# DB_Power-X03.net
KiCad netlist of a schematic drawn in Altium Designer
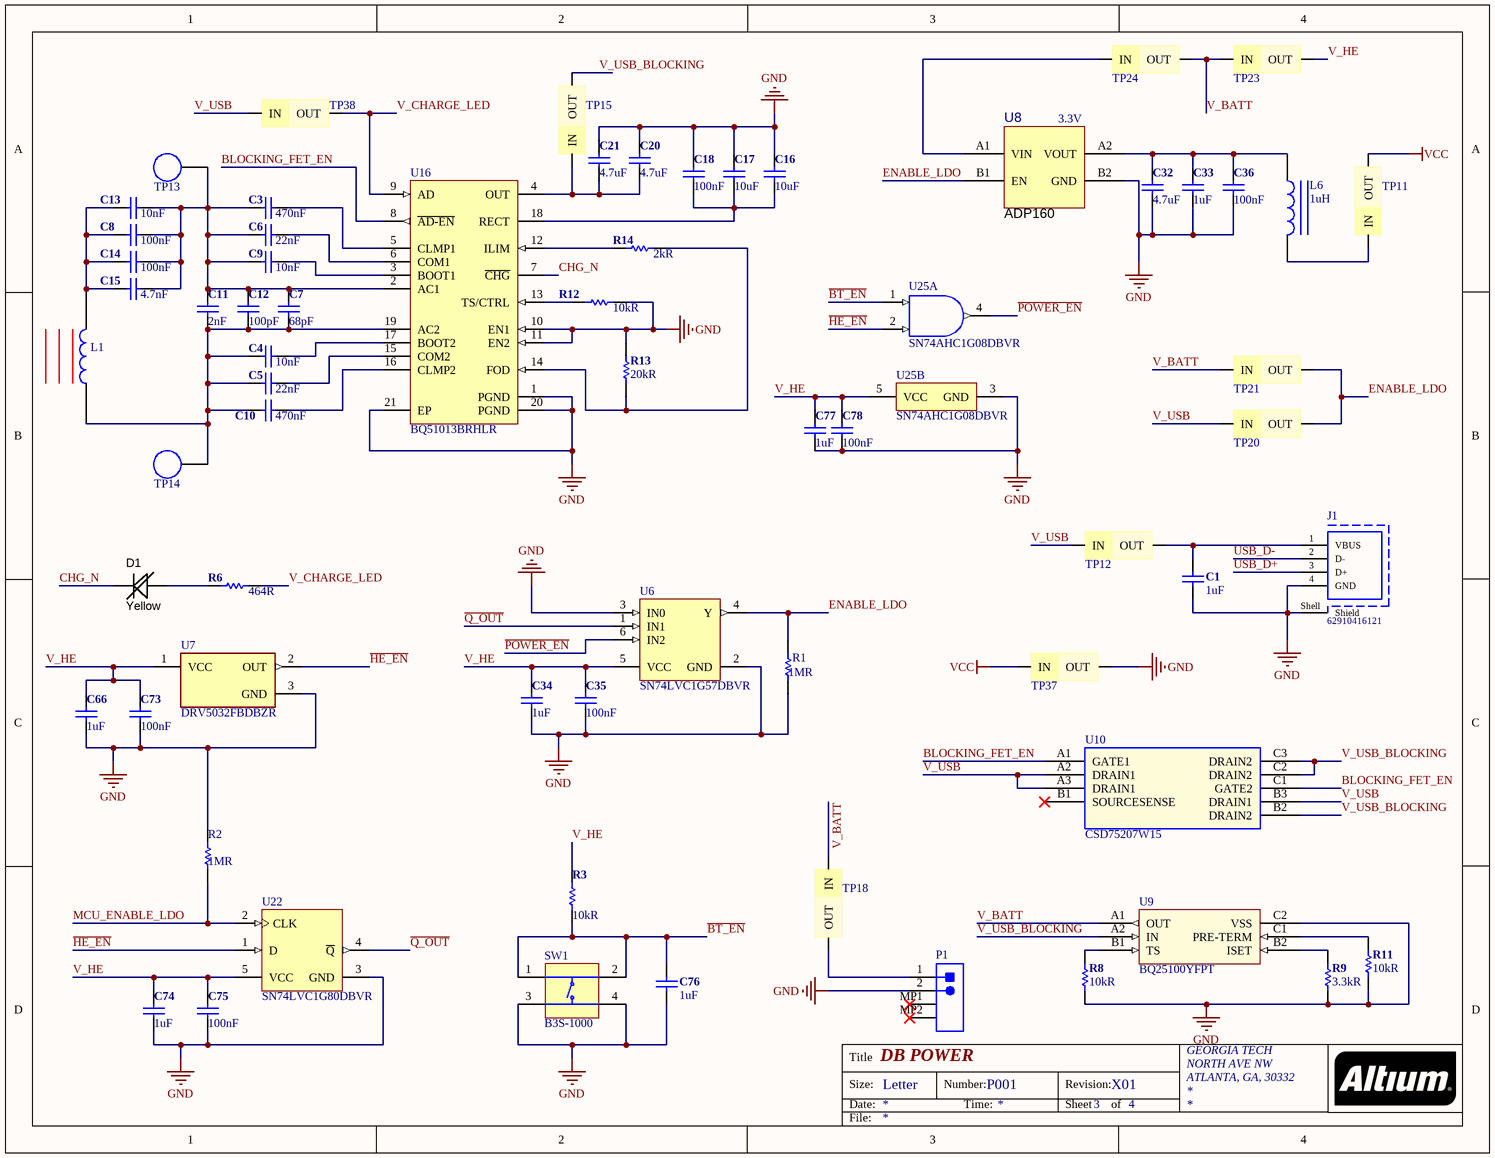
[diagram p0: DB_Power-X03.SchDoc]

(export (version "E")
  (design (tool "Eeschema 10.0.6"))
  (components
    (comp (ref "C1")
      (value "1uF")
      (footprint "C0402")
      (fields
        (field (name "MANUFACTURER") "Yageo")
        (field (name "MANUFACTURER PART NUMBER") "CC0402MRX5R5BB105")
        (field (name "TOLERANCE") "20%")
      )
      (libsource (lib "DB-X01") (part "C-0402(1005)"))
    )
    (comp (ref "C3")
      (value "470nF")
      (footprint "C0402")
      (fields
        (field (name "MANUFACTURER") "Murata")
        (field (name "MANUFACTURER PART NUMBER") "GRT155R61E474ME01D")
        (field (name "TOLERANCE") "20%")
      )
      (libsource (lib "DB-X01") (part "C-0402(1005)"))
    )
    (comp (ref "C4")
      (value "10nF")
      (footprint "C0402")
      (fields
        (field (name "MANUFACTURER") "KEMET")
        (field (name "MANUFACTURER PART NUMBER") "C0402C103J3RACTU")
        (field (name "TOLERANCE") "5%")
      )
      (libsource (lib "DB-X01") (part "C-0402(1005)"))
    )
    (comp (ref "C5")
      (value "22nF")
      (footprint "C0402")
      (fields
        (field (name "MANUFACTURER") "Murata")
        (field (name "MANUFACTURER PART NUMBER") "GRM155R71E223KA61D")
        (field (name "TOLERANCE") "10%")
      )
      (libsource (lib "DB-X01") (part "C-0402(1005)"))
    )
    (comp (ref "C6")
      (value "22nF")
      (footprint "C0402")
      (fields
        (field (name "MANUFACTURER") "Murata")
        (field (name "MANUFACTURER PART NUMBER") "GRM155R71E223KA61D")
        (field (name "TOLERANCE") "10%")
      )
      (libsource (lib "DB-X01") (part "C-0402(1005)"))
    )
    (comp (ref "C7")
      (value "68pF")
      (footprint "C0402")
      (fields
        (field (name "MANUFACTURER") "KEMET")
        (field (name "MANUFACTURER PART NUMBER") "CBR04C680F3GAC")
        (field (name "TOLERANCE") "1%")
      )
      (libsource (lib "DB-X01") (part "C-0402(1005)"))
    )
    (comp (ref "C8")
      (value "100nF")
      (footprint "C0402")
      (fields
        (field (name "MANUFACTURER") "Taiyo Yuden")
        (field (name "MANUFACTURER PART NUMBER") "TMK105BJ104KV-F")
        (field (name "TOLERANCE") "10%")
      )
      (libsource (lib "DB-X01") (part "C-0402(1005)"))
    )
    (comp (ref "C9")
      (value "10nF")
      (footprint "C0402")
      (fields
        (field (name "MANUFACTURER") "KEMET")
        (field (name "MANUFACTURER PART NUMBER") "C0402C103J3RACTU")
        (field (name "TOLERANCE") "5%")
      )
      (libsource (lib "DB-X01") (part "C-0402(1005)"))
    )
    (comp (ref "C10")
      (value "470nF")
      (footprint "C0402")
      (fields
        (field (name "MANUFACTURER") "Murata")
        (field (name "MANUFACTURER PART NUMBER") "GRT155R61E474ME01D")
        (field (name "TOLERANCE") "20%")
      )
      (libsource (lib "DB-X01") (part "C-0402(1005)"))
    )
    (comp (ref "C11")
      (value "2nF")
      (footprint "C0402")
      (fields
        (field (name "MANUFACTURER") "KEMET")
        (field (name "MANUFACTURER PART NUMBER") "C0402C202J3GACTU")
        (field (name "TOLERANCE") "5%")
      )
      (libsource (lib "DB-X01") (part "C-0402(1005)"))
    )
    (comp (ref "C12")
      (value "100pF")
      (footprint "C0402")
      (fields
        (field (name "MANUFACTURER") "KEMET")
        (field (name "MANUFACTURER PART NUMBER") "CBR04C101F3GAC")
        (field (name "TOLERANCE") "1%")
      )
      (libsource (lib "DB-X01") (part "C-0402(1005)"))
    )
    (comp (ref "C13")
      (value "10nF")
      (footprint "C0402")
      (fields
        (field (name "MANUFACTURER") "Yageo")
        (field (name "MANUFACTURER PART NUMBER") "CC0402JRX7R8BB103")
        (field (name "TOLERANCE") "5%")
      )
      (libsource (lib "DB-X01") (part "C-0402(1005)"))
    )
    (comp (ref "C14")
      (value "100nF")
      (footprint "C0402")
      (fields
        (field (name "MANUFACTURER") "Taiyo Yuden")
        (field (name "MANUFACTURER PART NUMBER") "TMK105BJ104KV-F")
        (field (name "TOLERANCE") "10%")
      )
      (libsource (lib "DB-X01") (part "C-0402(1005)"))
    )
    (comp (ref "C15")
      (value "4.7nF")
      (footprint "C0402")
      (fields
        (field (name "MANUFACTURER") "Yageo")
        (field (name "MANUFACTURER PART NUMBER") "CC0402JRX7R8BB472")
        (field (name "TOLERANCE") "5%")
      )
      (libsource (lib "DB-X01") (part "C-0402(1005)"))
    )
    (comp (ref "C16")
      (value "10uF")
      (footprint "C0603")
      (fields
        (field (name "MANUFACTURER") "Murata")
        (field (name "MANUFACTURER PART NUMBER") "GRM188R61E106MA73J")
        (field (name "TOLERANCE") "20%")
      )
      (libsource (lib "DB-X01") (part "C-0603(1608)"))
    )
    (comp (ref "C17")
      (value "10uF")
      (footprint "C0603")
      (fields
        (field (name "MANUFACTURER") "Murata")
        (field (name "MANUFACTURER PART NUMBER") "GRM188R61E106MA73J")
        (field (name "TOLERANCE") "20%")
      )
      (libsource (lib "DB-X01") (part "C-0603(1608)"))
    )
    (comp (ref "C18")
      (value "100nF")
      (footprint "C0603")
      (fields
        (field (name "MANUFACTURER") "Yageo")
        (field (name "MANUFACTURER PART NUMBER") "CC0402ZRY5V8BB104")
        (field (name "TOLERANCE") "80%")
      )
      (libsource (lib "DB-X01") (part "C-0603(1608)"))
    )
    (comp (ref "C20")
      (value "4.7uF")
      (footprint "C0402")
      (description "0402 10 V 4.7 uF ±20% Tolerance X5R Multilayer Ceramic Chip Capacitor")
      (fields
        (field (name "MANUFACTURER") "Murata")
        (field (name "MANUFACTURER PART NUMBER") "GRM155R61A475MEAAD")
      )
      (libsource (lib "DB-X01") (part "C-0402(1005)"))
    )
    (comp (ref "C21")
      (value "4.7uF")
      (footprint "C0402")
      (description "0402 10 V 4.7 uF ±20% Tolerance X5R Multilayer Ceramic Chip Capacitor")
      (fields
        (field (name "MANUFACTURER") "Murata")
        (field (name "MANUFACTURER PART NUMBER") "GRM155R61A475MEAAD")
      )
      (libsource (lib "DB-X01") (part "C-0402(1005)"))
    )
    (comp (ref "C32")
      (value "4.7uF")
      (footprint "C0402")
      (description "0402 10 V 4.7 uF ±20% Tolerance X5R Multilayer Ceramic Chip Capacitor")
      (fields
        (field (name "MANUFACTURER") "Murata")
        (field (name "MANUFACTURER PART NUMBER") "GRM155R61A475MEAAD")
      )
      (libsource (lib "DB-X01") (part "C-0402(1005)"))
    )
    (comp (ref "C33")
      (value "1uF")
      (footprint "C0402")
      (fields
        (field (name "MANUFACTURER") "Yageo")
        (field (name "MANUFACTURER PART NUMBER") "CC0402MRX5R5BB105")
        (field (name "TOLERANCE") "20%")
      )
      (libsource (lib "DB-X01") (part "C-0402(1005)"))
    )
    (comp (ref "C34")
      (value "1uF")
      (footprint "C0402")
      (fields
        (field (name "MANUFACTURER") "Yageo")
        (field (name "MANUFACTURER PART NUMBER") "CC0402MRX5R5BB105")
        (field (name "TOLERANCE") "20%")
      )
      (libsource (lib "DB-X01") (part "C-0402(1005)"))
    )
    (comp (ref "C35")
      (value "100nF")
      (footprint "C0402")
      (fields
        (field (name "MANUFACTURER") "Taiyo Yuden")
        (field (name "MANUFACTURER PART NUMBER") "TMK105BJ104KV-F")
        (field (name "TOLERANCE") "10%")
      )
      (libsource (lib "DB-X01") (part "C-0402(1005)"))
    )
    (comp (ref "C36")
      (value "100nF")
      (footprint "C0402")
      (fields
        (field (name "MANUFACTURER") "Taiyo Yuden")
        (field (name "MANUFACTURER PART NUMBER") "TMK105BJ104KV-F")
        (field (name "TOLERANCE") "10%")
      )
      (libsource (lib "DB-X01") (part "C-0402(1005)"))
    )
    (comp (ref "C66")
      (value "1uF")
      (footprint "C0402")
      (fields
        (field (name "MANUFACTURER") "Yageo")
        (field (name "MANUFACTURER PART NUMBER") "CC0402MRX5R5BB105")
        (field (name "TOLERANCE") "20%")
      )
      (libsource (lib "DB-X01") (part "C-0402(1005)"))
    )
    (comp (ref "C73")
      (value "100nF")
      (footprint "C0402")
      (fields
        (field (name "MANUFACTURER") "Taiyo Yuden")
        (field (name "MANUFACTURER PART NUMBER") "TMK105BJ104KV-F")
        (field (name "TOLERANCE") "10%")
      )
      (libsource (lib "DB-X01") (part "C-0402(1005)"))
    )
    (comp (ref "C74")
      (value "1uF")
      (footprint "C0402")
      (fields
        (field (name "MANUFACTURER") "Yageo")
        (field (name "MANUFACTURER PART NUMBER") "CC0402MRX5R5BB105")
        (field (name "TOLERANCE") "20%")
      )
      (libsource (lib "DB-X01") (part "C-0402(1005)"))
    )
    (comp (ref "C75")
      (value "100nF")
      (footprint "C0402")
      (fields
        (field (name "MANUFACTURER") "Taiyo Yuden")
        (field (name "MANUFACTURER PART NUMBER") "TMK105BJ104KV-F")
        (field (name "TOLERANCE") "10%")
      )
      (libsource (lib "DB-X01") (part "C-0402(1005)"))
    )
    (comp (ref "C76")
      (value "1uF")
      (footprint "C0402")
      (fields
        (field (name "MANUFACTURER") "Yageo")
        (field (name "MANUFACTURER PART NUMBER") "CC0402MRX5R5BB105")
        (field (name "TOLERANCE") "20%")
      )
      (libsource (lib "DB-X01") (part "C-0402(1005)"))
    )
    (comp (ref "C77")
      (value "1uF")
      (footprint "C0402")
      (fields
        (field (name "MANUFACTURER") "Yageo")
        (field (name "MANUFACTURER PART NUMBER") "CC0402MRX5R5BB105")
        (field (name "TOLERANCE") "20%")
      )
      (libsource (lib "DB-X01") (part "C-0402(1005)"))
    )
    (comp (ref "C78")
      (value "100nF")
      (footprint "C0402")
      (fields
        (field (name "MANUFACTURER") "Taiyo Yuden")
        (field (name "MANUFACTURER PART NUMBER") "TMK105BJ104KV-F")
        (field (name "TOLERANCE") "10%")
      )
      (libsource (lib "DB-X01") (part "C-0402(1005)"))
    )
    (comp (ref "D1")
      (value "Yellow")
      (footprint "LED_0402")
      (description "Single Color LED, Super Bright Yellow, Water Clear, 0.8mm")
      (fields
        (field (name "MANUFACTURER") "Kingbright")
        (field (name "MANUFACTURER PART NUMBER") "APHHS1005SYCK")
      )
      (libsource (lib "DB-X01") (part "LED_0402(1005)"))
    )
    (comp (ref "J1")
      (value "62910416121")
      (footprint "62910416121")
      (description "USB 2.0 Type B Receptacle WR-COM, Horizontal, SMT, with Pads and Pegs")
      (fields (field (name "MANUFACTURER") "Wurth Electronics"))
      (libsource (lib "Altium Content Vault") (part "WE-USB-4-1SHLD"))
    )
    (comp (ref "L1")
      (value "WIRELESS CHARGING COIL, RECEIVER")
      (footprint "760308101219")
      (description "General Purpose Inductor, 11.8uH, 10%, 1 Element")
      (fields
        (field (name "MANUFACTURER") "Wurth Electronics")
        (field (name "MANUFACTURER PART NUMBER") "760308101219")
      )
      (libsource (lib "DB-X01") (part "WIRELESS_CHARGING_COIL"))
    )
    (comp (ref "L6")
      (value "1uH")
      (footprint "L0402")
      (description "General Purpose Inductor, 1uH, 20%, 1 Element, Ferrite-Core, SMD, 0402")
      (fields
        (field (name "MANUFACTURER") "TDK")
        (field (name "MANUFACTURER PART NUMBER") "MLZ1005M1R0WT000")
      )
      (libsource (lib "DB-X01") (part "Inductor Iron"))
    )
    (comp (ref "P1")
      (value "B2B-PH-SM4-TB(LF)(SN)")
      (footprint "JST-B2B-PH-SM4-TB-2_V")
      (description "Male Header, Pitch 2 mm, 1 x 2 Position, Height 6.6 mm, RoHS, Tape and Reel")
      (fields (field (name "MANUFACTURER") "JST"))
      (libsource (lib "Altium Content Vault") (part "CN-1P-2M-R2"))
    )
    (comp (ref "R1")
      (value "AC0402FR-071ML")
      (footprint "RESC1005X37X25LL05T10")
      (description "100 ohm resistor")
      (fields
        (field (name "MANUFACTURER") "Yageo")
        (field (name "RESISTANCE") "1MR")
        (field (name "TOLERANCE") "1%")
      )
      (libsource (lib "Altium Content Vault") (part "RES"))
    )
    (comp (ref "R2")
      (value "AC0402FR-071ML")
      (footprint "RESC1005X37X25LL05T10")
      (description "100 ohm resistor")
      (fields
        (field (name "MANUFACTURER") "Yageo")
        (field (name "RESISTANCE") "1MR")
        (field (name "TOLERANCE") "1%")
      )
      (libsource (lib "Altium Content Vault") (part "RES"))
    )
    (comp (ref "R3")
      (value "10kR")
      (footprint "R0402")
      (fields
        (field (name "MANUFACTURER") "Yageo")
        (field (name "MANUFACTURER PART NUMBER") "AC0402FR-0710KL")
        (field (name "TOLERANCE") "1%")
      )
      (libsource (lib "DB-X01") (part "R-0402(1005)"))
    )
    (comp (ref "R6")
      (value "464R")
      (footprint "R0402")
      (fields
        (field (name "MANUFACTURER") "Yageo")
        (field (name "MANUFACTURER PART NUMBER") "RC0402FR-07464RL")
        (field (name "TOLERANCE") "1%")
      )
      (libsource (lib "DB-X01") (part "R-0402(1005)"))
    )
    (comp (ref "R8")
      (value "10kR")
      (footprint "R0402")
      (fields
        (field (name "MANUFACTURER") "Yageo")
        (field (name "MANUFACTURER PART NUMBER") "AC0402FR-0710KL")
        (field (name "TOLERANCE") "1%")
      )
      (libsource (lib "DB-X01") (part "R-0402(1005)"))
    )
    (comp (ref "R9")
      (value "3.3kR")
      (footprint "R0402")
      (fields
        (field (name "MANUFACTURER") "Yageo")
        (field (name "MANUFACTURER PART NUMBER") "AC0402FR-073K3L")
        (field (name "TOLERANCE") "1%")
      )
      (libsource (lib "DB-X01") (part "R-0402(1005)"))
    )
    (comp (ref "R11")
      (value "10kR")
      (footprint "R0402")
      (fields
        (field (name "MANUFACTURER") "Yageo")
        (field (name "MANUFACTURER PART NUMBER") "AC0402FR-0710KL")
        (field (name "TOLERANCE") "1%")
      )
      (libsource (lib "DB-X01") (part "R-0402(1005)"))
    )
    (comp (ref "R12")
      (value "10kR")
      (footprint "R0402")
      (fields
        (field (name "MANUFACTURER") "Yageo")
        (field (name "MANUFACTURER PART NUMBER") "AC0402FR-0710KL")
        (field (name "TOLERANCE") "1%")
      )
      (libsource (lib "DB-X01") (part "R-0402(1005)"))
    )
    (comp (ref "R13")
      (value "20kR")
      (footprint "R0402")
      (fields
        (field (name "MANUFACTURER") "Yageo")
        (field (name "MANUFACTURER PART NUMBER") "AC0402FR-0720KL")
        (field (name "TOLERANCE") "1%")
      )
      (libsource (lib "DB-X01") (part "R-0402(1005)"))
    )
    (comp (ref "R14")
      (value "2kR")
      (footprint "R0402")
      (fields
        (field (name "MANUFACTURER") "Yageo")
        (field (name "MANUFACTURER PART NUMBER") "AC0402FR-072KL")
        (field (name "TOLERANCE") "1%")
      )
      (libsource (lib "DB-X01") (part "R-0402(1005)"))
    )
    (comp (ref "SW1")
      (value "B3S-1000")
      (footprint "OMRON-B3S-1000-4_V")
      (description "Sealed Tactile Switch, SPST-NO, 3 to 24 V, -25 to 70 degC, 4-Pin SMD, RoHS, Bulk")
      (fields (field (name "MANUFACTURER") "Omron") (field (name "MANUFACTURER PART NUMBER") "B3S-1000P"))
      (libsource (lib "Altium Content Vault") (part "SW-SPST-4_A"))
    )
    (comp (ref "TP11")
      (value "JUMPER")
      (footprint "JUMPER")
      (description "SHUNT LP W/HANDLE 2 POS 30AU")
      (fields
        (field (name "MANUFACTURER") "TE Connectivity")
        (field (name "MANUFACTURER PART NUMBER") "8815452")
      )
      (libsource (lib "DB-X01") (part "JUMPER"))
    )
    (comp (ref "TP12")
      (value "JUMPER")
      (footprint "JUMPER")
      (description "SHUNT LP W/HANDLE 2 POS 30AU")
      (fields
        (field (name "MANUFACTURER") "TE Connectivity")
        (field (name "MANUFACTURER PART NUMBER") "8815452")
      )
      (libsource (lib "") (part "JUMPER_2"))
    )
    (comp (ref "TP13")
      (value "S1751-46R")
      (footprint "S1751-46R")
      (description "PC TEST POINT TIN SMD")
      (fields (field (name "MANUFACTURER") "Harwin Inc."))
      (libsource (lib "DB-X01") (part "S1751-46R"))
    )
    (comp (ref "TP14")
      (value "S1751-46R")
      (footprint "S1751-46R")
      (description "PC TEST POINT TIN SMD")
      (fields (field (name "MANUFACTURER") "Harwin Inc."))
      (libsource (lib "DB-X01") (part "S1751-46R"))
    )
    (comp (ref "TP15")
      (value "JUMPER")
      (footprint "JUMPER")
      (description "SHUNT LP W/HANDLE 2 POS 30AU")
      (fields
        (field (name "MANUFACTURER") "TE Connectivity")
        (field (name "MANUFACTURER PART NUMBER") "8815452")
      )
      (libsource (lib "DB-X01") (part "JUMPER"))
    )
    (comp (ref "TP18")
      (value "JUMPER")
      (footprint "JUMPER")
      (description "SHUNT LP W/HANDLE 2 POS 30AU")
      (fields
        (field (name "MANUFACTURER") "TE Connectivity")
        (field (name "MANUFACTURER PART NUMBER") "8815452")
      )
      (libsource (lib "") (part "JUMPER_1"))
    )
    (comp (ref "TP20")
      (value "JUMPER")
      (footprint "JUMPER")
      (description "SHUNT LP W/HANDLE 2 POS 30AU")
      (fields
        (field (name "MANUFACTURER") "TE Connectivity")
        (field (name "MANUFACTURER PART NUMBER") "8815452")
      )
      (libsource (lib "") (part "JUMPER_2"))
    )
    (comp (ref "TP21")
      (value "JUMPER")
      (footprint "JUMPER")
      (description "SHUNT LP W/HANDLE 2 POS 30AU")
      (fields
        (field (name "MANUFACTURER") "TE Connectivity")
        (field (name "MANUFACTURER PART NUMBER") "8815452")
      )
      (libsource (lib "") (part "JUMPER_2"))
    )
    (comp (ref "TP23")
      (value "JUMPER")
      (footprint "JUMPER")
      (description "SHUNT LP W/HANDLE 2 POS 30AU")
      (fields
        (field (name "MANUFACTURER") "TE Connectivity")
        (field (name "MANUFACTURER PART NUMBER") "8815452")
      )
      (libsource (lib "DB-X02") (part "JUMPER"))
    )
    (comp (ref "TP24")
      (value "JUMPER")
      (footprint "JUMPER")
      (description "SHUNT LP W/HANDLE 2 POS 30AU")
      (fields
        (field (name "MANUFACTURER") "TE Connectivity")
        (field (name "MANUFACTURER PART NUMBER") "8815452")
      )
      (libsource (lib "DB-X02") (part "JUMPER"))
    )
    (comp (ref "TP37")
      (value "JUMPER")
      (footprint "JUMPER")
      (description "SHUNT LP W/HANDLE 2 POS 30AU")
      (fields
        (field (name "MANUFACTURER") "TE Connectivity")
        (field (name "MANUFACTURER PART NUMBER") "8815452")
      )
      (libsource (lib "DB-X02") (part "JUMPER"))
    )
    (comp (ref "TP38")
      (value "JUMPER")
      (footprint "JUMPER")
      (description "SHUNT LP W/HANDLE 2 POS 30AU")
      (fields
        (field (name "MANUFACTURER") "TE Connectivity")
        (field (name "MANUFACTURER PART NUMBER") "8815452")
      )
      (libsource (lib "DB-X02") (part "JUMPER"))
    )
    (comp (ref "U6")
      (value "SN74LVC1G57DBVR")
      (footprint "DBV0006A_M")
      (description "CONFIGURABLE MULTIPLE-FUNCTION GATE, DBV0006A, LARGE T&R")
      (fields (field (name "MANUFACTURER") "Texas Instruments"))
      (libsource (lib "Altium Content Vault") (part "TI-SN74XXX1GXX-6"))
    )
    (comp (ref "U7")
      (value "DRV5032FBDBZR")
      (footprint "FP-DBZ0003A-MFG")
      (description "LP HALL 32FBDBZR")
      (fields (field (name "MANUFACTURER") "Texas Instruments"))
      (libsource (lib "Altium Content Vault") (part "2ac151be60cf6bda0d169f73a696793"))
    )
    (comp (ref "U8")
      (value "ADP160")
      (footprint "ADP160")
      (description "Fixed Positive LDO Regulator, 3.3V, 0.195V Dropout, CMOS, PBGA4")
      (fields
        (field (name "MANUFACTURER") "Analog Devices")
        (field (name "MANUFACTURER PART NUMBER") "ADP160ACBZ-3.3-R7")
        (field (name "OUTPUT VOLTAGE") "3.3V")
      )
      (libsource (lib "DB-X01") (part "ADP160-3_3V"))
    )
    (comp (ref "U9")
      (value "BQ25100YFPT")
      (footprint "YZP0006")
      (description "Power Supply Support Circuit")
      (fields (field (name "MANUFACTURER") "Texas Instruments"))
      (libsource (lib "DB-X01") (part "BQ25100YFPT"))
    )
    (comp (ref "U10")
      (value "CSD75207W15")
      (footprint "YZF0009")
      (description "Small Signal Field-Effect Transistor, P-Channel, Metal-oxide Semiconductor FET")
      (fields (field (name "MANUFACTURER") "Texas Instruments"))
      (libsource (lib "DB-X01") (part "CSD75207W15"))
    )
    (comp (ref "U16")
      (value "BQ51013BRHLR")
      (footprint "BQ51013BRHLR")
      (fields (field (name "MANUFACTURER") "Texas Instruments"))
      (libsource (lib "DB-X01") (part "TI-BQ51013B-RHL20"))
    )
    (comp (ref "U22")
      (value "SN74LVC1G80DBVR")
      (footprint "DBV0005A_N")
      (description "Single Positive-Edge-Triggered D-Type Flip-Flop, DBV0005A, LARGE T&R")
      (fields (field (name "MANUFACTURER") "Texas Instruments"))
      (libsource (lib "Altium Content Vault") (part "TI-SN74XXX1G80-5"))
    )
    (comp (ref "U25")
      (value "SN74AHC1G08DBVR")
      (footprint "DBV0005A_N")
      (description "Single 2-Input Positive-AND Gate, DBV0005A, LARGE T&R")
      (fields (field (name "MANUFACTURER") "Texas Instruments"))
      (libsource (lib "Altium Content Vault") (part "TI-SN74XXX1X08-5"))
    )
  )
  (nets
    (net (code "1") (name "/BLOCKING_FET_EN") (class "Default")
      (node (ref "U10") (pin "A1") (pinfunction "GATE1_A1") (pintype "passive"))
      (node (ref "U10") (pin "C1") (pinfunction "GATE2_C1") (pintype "passive"))
      (node (ref "U16") (pin "8") (pinfunction "~{AD-EN}_8") (pintype "output"))
    )
    (net (code "2") (name "/CHG_N") (class "Default")
      (node (ref "D1") (pin "K") (pinfunction "K_K") (pintype "passive"))
      (node (ref "U16") (pin "7") (pinfunction "~{CHG}_7") (pintype "open_collector"))
    )
    (net (code "3") (name "/ENABLE_LDO") (class "Default")
      (node (ref "R1") (pin "1") (pinfunction "1_1") (pintype "passive"))
      (node (ref "TP20") (pin "2") (pinfunction "OUT_2") (pintype "passive"))
      (node (ref "TP21") (pin "2") (pinfunction "OUT_2") (pintype "passive"))
      (node (ref "U6") (pin "4") (pinfunction "Y_4") (pintype "output"))
      (node (ref "U8") (pin "B1") (pinfunction "EN_B1") (pintype "passive"))
    )
    (net (code "4") (name "/MCU_ENABLE_LDO") (class "Default")
      (node (ref "R2") (pin "1") (pinfunction "1_1") (pintype "passive"))
      (node (ref "U22") (pin "2") (pinfunction "CLK_2") (pintype "input"))
    )
    (net (code "5") (name "/USB_D+") (class "Default")
      (node (ref "J1") (pin "3") (pinfunction "D+_3") (pintype "passive"))
    )
    (net (code "6") (name "/USB_D-") (class "Default")
      (node (ref "J1") (pin "2") (pinfunction "D-_2") (pintype "passive"))
    )
    (net (code "7") (name "/V_BATT") (class "Default")
      (node (ref "TP18") (pin "1") (pinfunction "IN_1") (pintype "passive"))
      (node (ref "TP21") (pin "1") (pinfunction "IN_1") (pintype "passive"))
      (node (ref "TP23") (pin "1") (pinfunction "IN_1") (pintype "passive"))
      (node (ref "TP24") (pin "2") (pinfunction "OUT_2") (pintype "passive"))
      (node (ref "U9") (pin "A1") (pinfunction "OUT_A1") (pintype "output"))
    )
    (net (code "8") (name "/V_CHARGE_LED") (class "Default")
      (node (ref "R6") (pin "2") (pinfunction "2_2") (pintype "passive"))
      (node (ref "TP38") (pin "2") (pinfunction "OUT_2") (pintype "passive"))
      (node (ref "U16") (pin "9") (pinfunction "AD_9") (pintype "input"))
    )
    (net (code "9") (name "/V_HE") (class "Default")
      (node (ref "C34") (pin "1") (pinfunction "1_1") (pintype "passive"))
      (node (ref "C35") (pin "2") (pinfunction "2_2") (pintype "passive"))
      (node (ref "C66") (pin "1") (pinfunction "1_1") (pintype "passive"))
      (node (ref "C73") (pin "2") (pinfunction "2_2") (pintype "passive"))
      (node (ref "C74") (pin "1") (pinfunction "1_1") (pintype "passive"))
      (node (ref "C75") (pin "2") (pinfunction "2_2") (pintype "passive"))
      (node (ref "C77") (pin "1") (pinfunction "1_1") (pintype "passive"))
      (node (ref "C78") (pin "2") (pinfunction "2_2") (pintype "passive"))
      (node (ref "R3") (pin "1") (pinfunction "1_1") (pintype "passive"))
      (node (ref "TP23") (pin "2") (pinfunction "OUT_2") (pintype "passive"))
      (node (ref "U22") (pin "5") (pinfunction "VCC_5") (pintype "power_in"))
      (node (ref "U25") (pin "5") (pinfunction "VCC_5") (pintype "power_in"))
      (node (ref "U6") (pin "5") (pinfunction "VCC_5") (pintype "power_in"))
      (node (ref "U7") (pin "1") (pinfunction "VCC_1") (pintype "power_in"))
    )
    (net (code "10") (name "/V_USB") (class "Default")
      (node (ref "TP12") (pin "1") (pinfunction "IN_1") (pintype "passive"))
      (node (ref "TP20") (pin "1") (pinfunction "IN_1") (pintype "passive"))
      (node (ref "TP38") (pin "1") (pinfunction "IN_1") (pintype "passive"))
      (node (ref "U10") (pin "A2") (pinfunction "DRAIN1_A2") (pintype "passive"))
      (node (ref "U10") (pin "A3") (pinfunction "DRAIN1_A3") (pintype "passive"))
      (node (ref "U10") (pin "B3") (pinfunction "DRAIN1_B3") (pintype "passive"))
    )
    (net (code "11") (name "/V_USB_BLOCKING") (class "Default")
      (node (ref "TP15") (pin "2") (pinfunction "OUT_2") (pintype "passive"))
      (node (ref "U10") (pin "B2") (pinfunction "DRAIN2_B2") (pintype "passive"))
      (node (ref "U10") (pin "C2") (pinfunction "DRAIN2_C2") (pintype "passive"))
      (node (ref "U10") (pin "C3") (pinfunction "DRAIN2_C3") (pintype "passive"))
      (node (ref "U9") (pin "A2") (pinfunction "IN_A2") (pintype "input"))
    )
    (net (code "12") (name "/~{BT_EN}") (class "Default")
      (node (ref "C76") (pin "2") (pinfunction "2_2") (pintype "passive"))
      (node (ref "R3") (pin "2") (pinfunction "2_2") (pintype "passive"))
      (node (ref "SW1") (pin "1") (pinfunction "1_1") (pintype "passive"))
      (node (ref "SW1") (pin "2") (pinfunction "2_2") (pintype "passive"))
      (node (ref "U25") (pin "1") (pinfunction "A_1") (pintype "input"))
    )
    (net (code "13") (name "/~{HE_EN}") (class "Default")
      (node (ref "U22") (pin "1") (pinfunction "D_1") (pintype "input"))
      (node (ref "U25") (pin "2") (pinfunction "B_2") (pintype "input"))
      (node (ref "U7") (pin "2") (pinfunction "OUT_2") (pintype "output"))
    )
    (net (code "14") (name "/~{POWER_EN}") (class "Default")
      (node (ref "U25") (pin "4") (pinfunction "Y_4") (pintype "output"))
      (node (ref "U6") (pin "6") (pinfunction "IN2_6") (pintype "input"))
    )
    (net (code "15") (name "/~{Q_OUT}") (class "Default")
      (node (ref "U22") (pin "4") (pinfunction "~{Q}_4") (pintype "output"))
      (node (ref "U6") (pin "1") (pinfunction "IN1_1") (pintype "input"))
    )
    (net (code "16") (name "GND") (class "Default")
      (node (ref "C1") (pin "2") (pinfunction "2_2") (pintype "passive"))
      (node (ref "C16") (pin "2") (pinfunction "2_2") (pintype "passive"))
      (node (ref "C17") (pin "2") (pinfunction "2_2") (pintype "passive"))
      (node (ref "C18") (pin "2") (pinfunction "2_2") (pintype "passive"))
      (node (ref "C20") (pin "1") (pinfunction "1_1") (pintype "passive"))
      (node (ref "C21") (pin "1") (pinfunction "1_1") (pintype "passive"))
      (node (ref "C32") (pin "2") (pinfunction "2_2") (pintype "passive"))
      (node (ref "C33") (pin "2") (pinfunction "2_2") (pintype "passive"))
      (node (ref "C34") (pin "2") (pinfunction "2_2") (pintype "passive"))
      (node (ref "C35") (pin "1") (pinfunction "1_1") (pintype "passive"))
      (node (ref "C36") (pin "1") (pinfunction "1_1") (pintype "passive"))
      (node (ref "C66") (pin "2") (pinfunction "2_2") (pintype "passive"))
      (node (ref "C73") (pin "1") (pinfunction "1_1") (pintype "passive"))
      (node (ref "C74") (pin "2") (pinfunction "2_2") (pintype "passive"))
      (node (ref "C75") (pin "1") (pinfunction "1_1") (pintype "passive"))
      (node (ref "C76") (pin "1") (pinfunction "1_1") (pintype "passive"))
      (node (ref "C77") (pin "2") (pinfunction "2_2") (pintype "passive"))
      (node (ref "C78") (pin "1") (pinfunction "1_1") (pintype "passive"))
      (node (ref "J1") (pin "4") (pinfunction "GND_4") (pintype "passive"))
      (node (ref "J1") (pin "Shell") (pinfunction "Shield_Shell") (pintype "passive"))
      (node (ref "P1") (pin "2") (pinfunction "2_2") (pintype "passive"))
      (node (ref "R1") (pin "2") (pinfunction "2_2") (pintype "passive"))
      (node (ref "R11") (pin "1") (pinfunction "1_1") (pintype "passive"))
      (node (ref "R12") (pin "2") (pinfunction "2_2") (pintype "passive"))
      (node (ref "R13") (pin "2") (pinfunction "2_2") (pintype "passive"))
      (node (ref "R2") (pin "2") (pinfunction "2_2") (pintype "passive"))
      (node (ref "R8") (pin "1") (pinfunction "1_1") (pintype "passive"))
      (node (ref "R9") (pin "1") (pinfunction "1_1") (pintype "passive"))
      (node (ref "SW1") (pin "3") (pinfunction "3_3") (pintype "passive"))
      (node (ref "SW1") (pin "4") (pinfunction "4_4") (pintype "passive"))
      (node (ref "TP37") (pin "2") (pinfunction "OUT_2") (pintype "passive"))
      (node (ref "U16") (pin "1") (pinfunction "PGND_1") (pintype "power_in"))
      (node (ref "U16") (pin "10") (pinfunction "EN1_10") (pintype "input"))
      (node (ref "U16") (pin "11") (pinfunction "EN2_11") (pintype "input"))
      (node (ref "U16") (pin "20") (pinfunction "PGND_20") (pintype "power_in"))
      (node (ref "U16") (pin "21") (pinfunction "EP_21") (pintype "passive"))
      (node (ref "U22") (pin "3") (pinfunction "GND_3") (pintype "power_in"))
      (node (ref "U25") (pin "3") (pinfunction "GND_3") (pintype "power_in"))
      (node (ref "U6") (pin "2") (pinfunction "GND_2") (pintype "power_in"))
      (node (ref "U6") (pin "3") (pinfunction "IN0_3") (pintype "input"))
      (node (ref "U7") (pin "3") (pinfunction "GND_3") (pintype "power_in"))
      (node (ref "U8") (pin "B2") (pinfunction "GND_B2") (pintype "passive"))
      (node (ref "U9") (pin "C2") (pinfunction "VSS_C2") (pintype "power_in"))
    )
    (net (code "17") (name "Net-(C13-Pad1)") (class "Default")
      (node (ref "C13") (pin "1") (pinfunction "1_1") (pintype "passive"))
      (node (ref "C14") (pin "1") (pinfunction "1_1") (pintype "passive"))
      (node (ref "C15") (pin "1") (pinfunction "1_1") (pintype "passive"))
      (node (ref "C8") (pin "1") (pinfunction "1_1") (pintype "passive"))
      (node (ref "L1") (pin "2") (pinfunction "2_2") (pintype "passive"))
    )
    (net (code "18") (name "Net-(D1-PadA)") (class "Default")
      (node (ref "D1") (pin "A") (pinfunction "A_A") (pintype "passive"))
      (node (ref "R6") (pin "1") (pinfunction "1_1") (pintype "passive"))
    )
    (net (code "19") (name "Net-(J1-VBUS)") (class "Default")
      (node (ref "C1") (pin "1") (pinfunction "1_1") (pintype "passive"))
      (node (ref "J1") (pin "1") (pinfunction "VBUS_1") (pintype "passive"))
      (node (ref "TP12") (pin "2") (pinfunction "OUT_2") (pintype "passive"))
    )
    (net (code "20") (name "Net-(TP11-IN)") (class "Default")
      (node (ref "L6") (pin "2") (pinfunction "2_2") (pintype "passive"))
      (node (ref "TP11") (pin "1") (pinfunction "IN_1") (pintype "passive"))
    )
    (net (code "21") (name "Net-(TP15-IN)") (class "Default")
      (node (ref "C20") (pin "2") (pinfunction "2_2") (pintype "passive"))
      (node (ref "C21") (pin "2") (pinfunction "2_2") (pintype "passive"))
      (node (ref "TP15") (pin "1") (pinfunction "IN_1") (pintype "passive"))
      (node (ref "U16") (pin "4") (pinfunction "OUT_4") (pintype "power_in"))
    )
    (net (code "22") (name "Net-(TP18-OUT)") (class "Default")
      (node (ref "P1") (pin "1") (pinfunction "1_1") (pintype "passive"))
      (node (ref "TP18") (pin "2") (pinfunction "OUT_2") (pintype "passive"))
    )
    (net (code "23") (name "Net-(TP24-IN)") (class "Default")
      (node (ref "TP24") (pin "1") (pinfunction "IN_1") (pintype "passive"))
      (node (ref "U8") (pin "A1") (pinfunction "VIN_A1") (pintype "passive"))
    )
    (net (code "24") (name "Net-(U8-VOUT)") (class "Default")
      (node (ref "C32") (pin "1") (pinfunction "1_1") (pintype "passive"))
      (node (ref "C33") (pin "1") (pinfunction "1_1") (pintype "passive"))
      (node (ref "C36") (pin "2") (pinfunction "2_2") (pintype "passive"))
      (node (ref "L6") (pin "1") (pinfunction "1_1") (pintype "passive"))
      (node (ref "U8") (pin "A2") (pinfunction "VOUT_A2") (pintype "passive"))
    )
    (net (code "25") (name "Net-(U9-ISET)") (class "Default")
      (node (ref "R9") (pin "2") (pinfunction "2_2") (pintype "passive"))
      (node (ref "U9") (pin "B2") (pinfunction "ISET_B2") (pintype "input"))
    )
    (net (code "26") (name "Net-(U9-PRE-TERM)") (class "Default")
      (node (ref "R11") (pin "2") (pinfunction "2_2") (pintype "passive"))
      (node (ref "U9") (pin "C1") (pinfunction "PRE-TERM_C1") (pintype "input"))
    )
    (net (code "27") (name "Net-(U9-TS)") (class "Default")
      (node (ref "R8") (pin "2") (pinfunction "2_2") (pintype "passive"))
      (node (ref "U9") (pin "B1") (pinfunction "TS_B1") (pintype "input"))
    )
    (net (code "28") (name "Net-(U16-AC1)") (class "Default")
      (node (ref "C11") (pin "1") (pinfunction "1_1") (pintype "passive"))
      (node (ref "C12") (pin "1") (pinfunction "1_1") (pintype "passive"))
      (node (ref "C13") (pin "2") (pinfunction "2_2") (pintype "passive"))
      (node (ref "C14") (pin "2") (pinfunction "2_2") (pintype "passive"))
      (node (ref "C15") (pin "2") (pinfunction "2_2") (pintype "passive"))
      (node (ref "C3") (pin "1") (pinfunction "1_1") (pintype "passive"))
      (node (ref "C6") (pin "1") (pinfunction "1_1") (pintype "passive"))
      (node (ref "C7") (pin "1") (pinfunction "1_1") (pintype "passive"))
      (node (ref "C8") (pin "2") (pinfunction "2_2") (pintype "passive"))
      (node (ref "C9") (pin "1") (pinfunction "1_1") (pintype "passive"))
      (node (ref "TP13") (pin "1") (pinfunction "1_1") (pintype "passive"))
      (node (ref "U16") (pin "2") (pinfunction "AC1_2") (pintype "power_in"))
    )
    (net (code "29") (name "Net-(U16-AC2)") (class "Default")
      (node (ref "C10") (pin "1") (pinfunction "1_1") (pintype "passive"))
      (node (ref "C11") (pin "2") (pinfunction "2_2") (pintype "passive"))
      (node (ref "C12") (pin "2") (pinfunction "2_2") (pintype "passive"))
      (node (ref "C4") (pin "1") (pinfunction "1_1") (pintype "passive"))
      (node (ref "C5") (pin "1") (pinfunction "1_1") (pintype "passive"))
      (node (ref "C7") (pin "2") (pinfunction "2_2") (pintype "passive"))
      (node (ref "L1") (pin "1") (pinfunction "1_1") (pintype "passive"))
      (node (ref "TP14") (pin "1") (pinfunction "1_1") (pintype "passive"))
      (node (ref "U16") (pin "19") (pinfunction "AC2_19") (pintype "power_in"))
    )
    (net (code "30") (name "Net-(U16-BOOT1)") (class "Default")
      (node (ref "C9") (pin "2") (pinfunction "2_2") (pintype "passive"))
      (node (ref "U16") (pin "3") (pinfunction "BOOT1_3") (pintype "passive"))
    )
    (net (code "31") (name "Net-(U16-BOOT2)") (class "Default")
      (node (ref "C4") (pin "2") (pinfunction "2_2") (pintype "passive"))
      (node (ref "U16") (pin "17") (pinfunction "BOOT2_17") (pintype "passive"))
    )
    (net (code "32") (name "Net-(U16-CLMP1)") (class "Default")
      (node (ref "C3") (pin "2") (pinfunction "2_2") (pintype "passive"))
      (node (ref "U16") (pin "5") (pinfunction "CLMP1_5") (pintype "open_collector"))
    )
    (net (code "33") (name "Net-(U16-CLMP2)") (class "Default")
      (node (ref "C10") (pin "2") (pinfunction "2_2") (pintype "passive"))
      (node (ref "U16") (pin "16") (pinfunction "CLMP2_16") (pintype "open_collector"))
    )
    (net (code "34") (name "Net-(U16-COM1)") (class "Default")
      (node (ref "C6") (pin "2") (pinfunction "2_2") (pintype "passive"))
      (node (ref "U16") (pin "6") (pinfunction "COM1_6") (pintype "open_collector"))
    )
    (net (code "35") (name "Net-(U16-COM2)") (class "Default")
      (node (ref "C5") (pin "2") (pinfunction "2_2") (pintype "passive"))
      (node (ref "U16") (pin "15") (pinfunction "COM2_15") (pintype "open_collector"))
    )
    (net (code "36") (name "Net-(U16-FOD)") (class "Default")
      (node (ref "R13") (pin "1") (pinfunction "1_1") (pintype "passive"))
      (node (ref "R14") (pin "2") (pinfunction "2_2") (pintype "passive"))
      (node (ref "U16") (pin "14") (pinfunction "FOD_14") (pintype "input"))
    )
    (net (code "37") (name "Net-(U16-ILIM)") (class "Default")
      (node (ref "R14") (pin "1") (pinfunction "1_1") (pintype "passive"))
      (node (ref "U16") (pin "12") (pinfunction "ILIM_12") (pintype "input"))
    )
    (net (code "38") (name "Net-(U16-RECT)") (class "Default")
      (node (ref "C16") (pin "1") (pinfunction "1_1") (pintype "passive"))
      (node (ref "C17") (pin "1") (pinfunction "1_1") (pintype "passive"))
      (node (ref "C18") (pin "1") (pinfunction "1_1") (pintype "passive"))
      (node (ref "U16") (pin "18") (pinfunction "RECT_18") (pintype "passive"))
    )
    (net (code "39") (name "Net-(U16-TS{slash}CTRL)") (class "Default")
      (node (ref "R12") (pin "1") (pinfunction "1_1") (pintype "passive"))
      (node (ref "U16") (pin "13") (pinfunction "TS/CTRL_13") (pintype "input"))
    )
    (net (code "40") (name "VCC") (class "Default")
      (node (ref "TP11") (pin "2") (pinfunction "OUT_2") (pintype "passive"))
      (node (ref "TP37") (pin "1") (pinfunction "IN_1") (pintype "passive"))
    )
    (net (code "41") (name "unconnected-(P1-PadMP1)") (class "Default")
      (node (ref "P1") (pin "MP1") (pinfunction "MP1_MP1") (pintype "passive+no_connect"))
    )
    (net (code "42") (name "unconnected-(P1-PadMP2)") (class "Default")
      (node (ref "P1") (pin "MP2") (pinfunction "MP2_MP2") (pintype "passive+no_connect"))
    )
    (net (code "43") (name "unconnected-(U10-SOURCESENSE-PadB1)") (class "Default")
      (node (ref "U10") (pin "B1") (pinfunction "SOURCESENSE_B1") (pintype "passive+no_connect"))
    )
  )
)
